# pcb_2.net
KiCad netlist of a schematic drawn in EAGLE
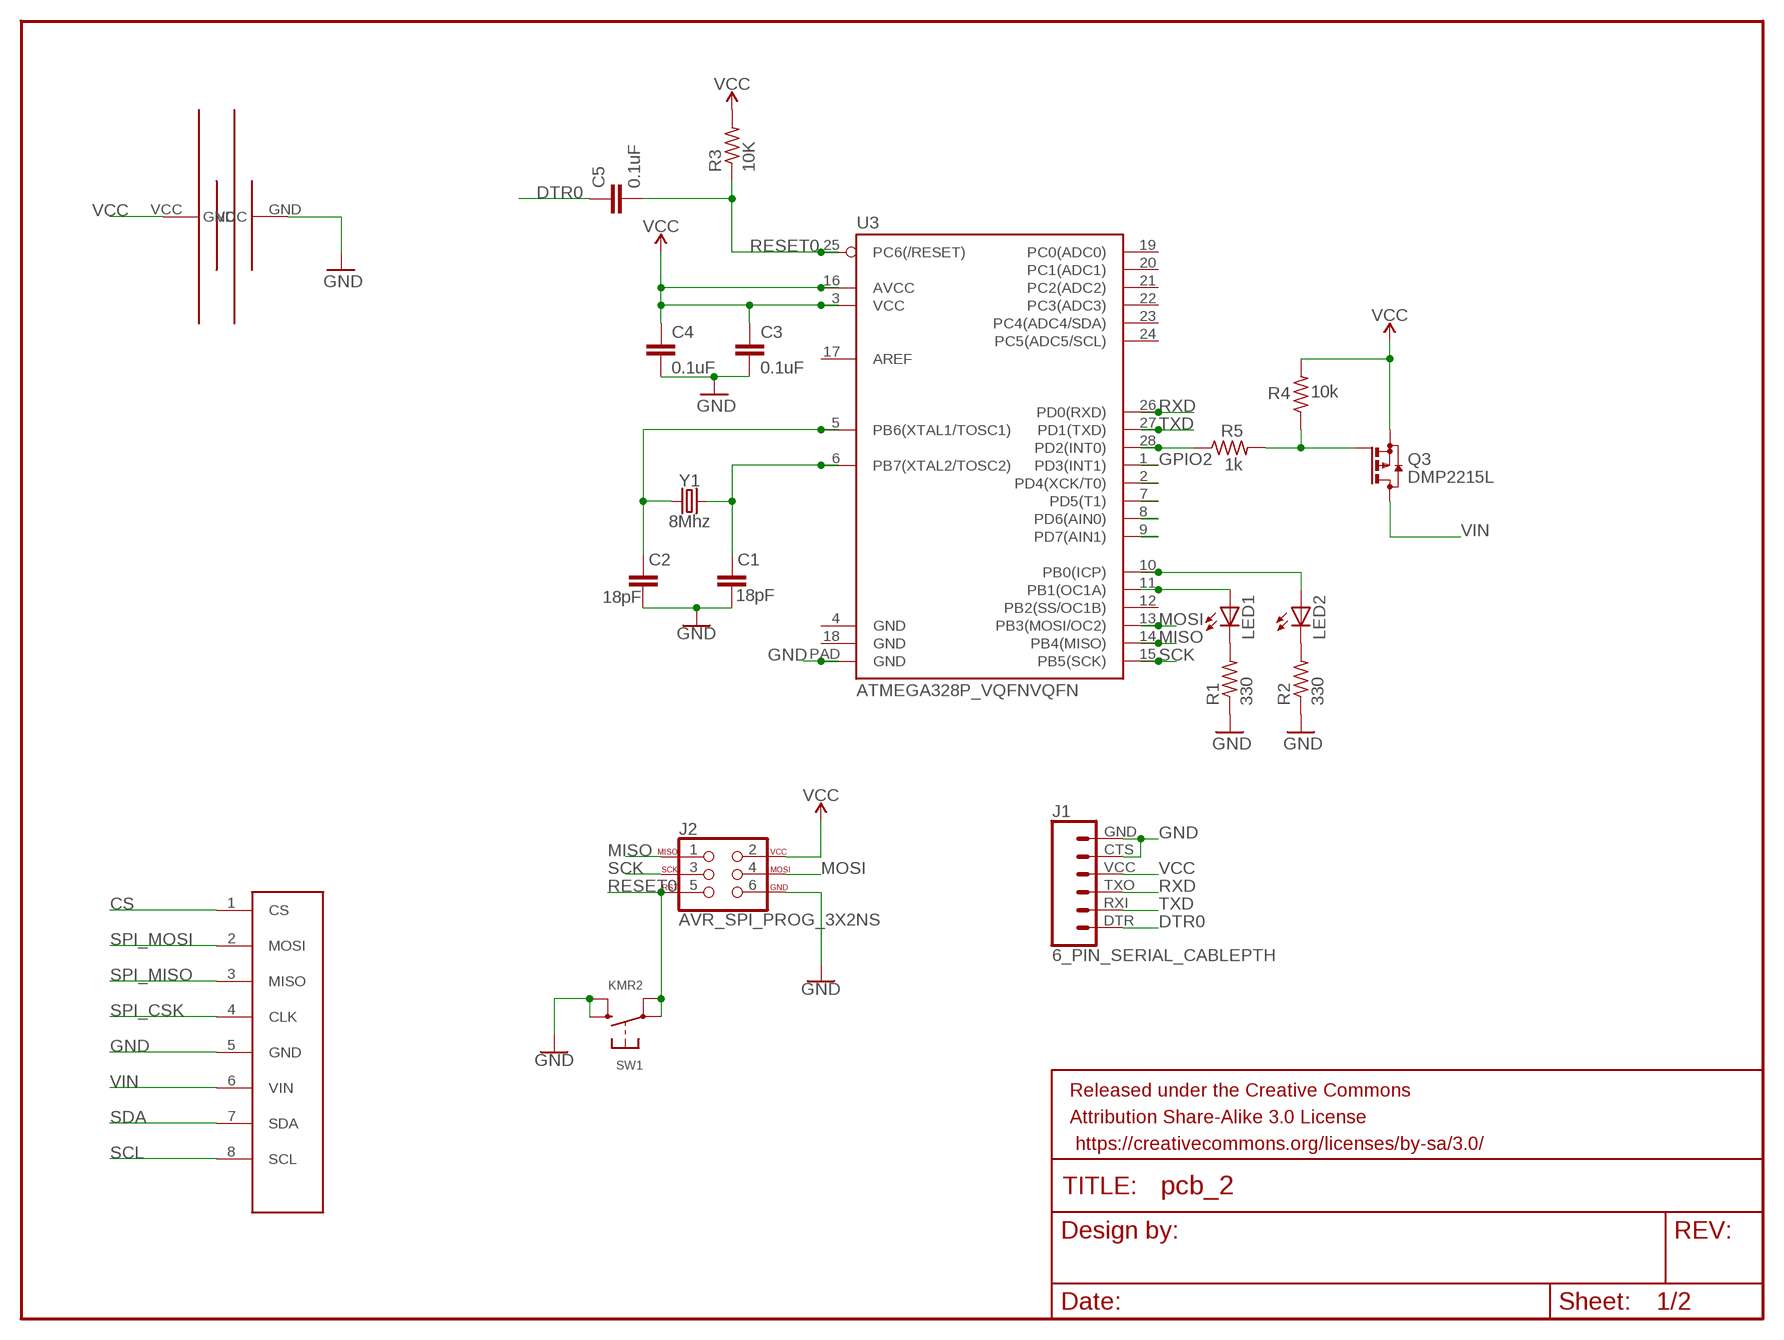
[diagram p0: schematic, sheet 1]
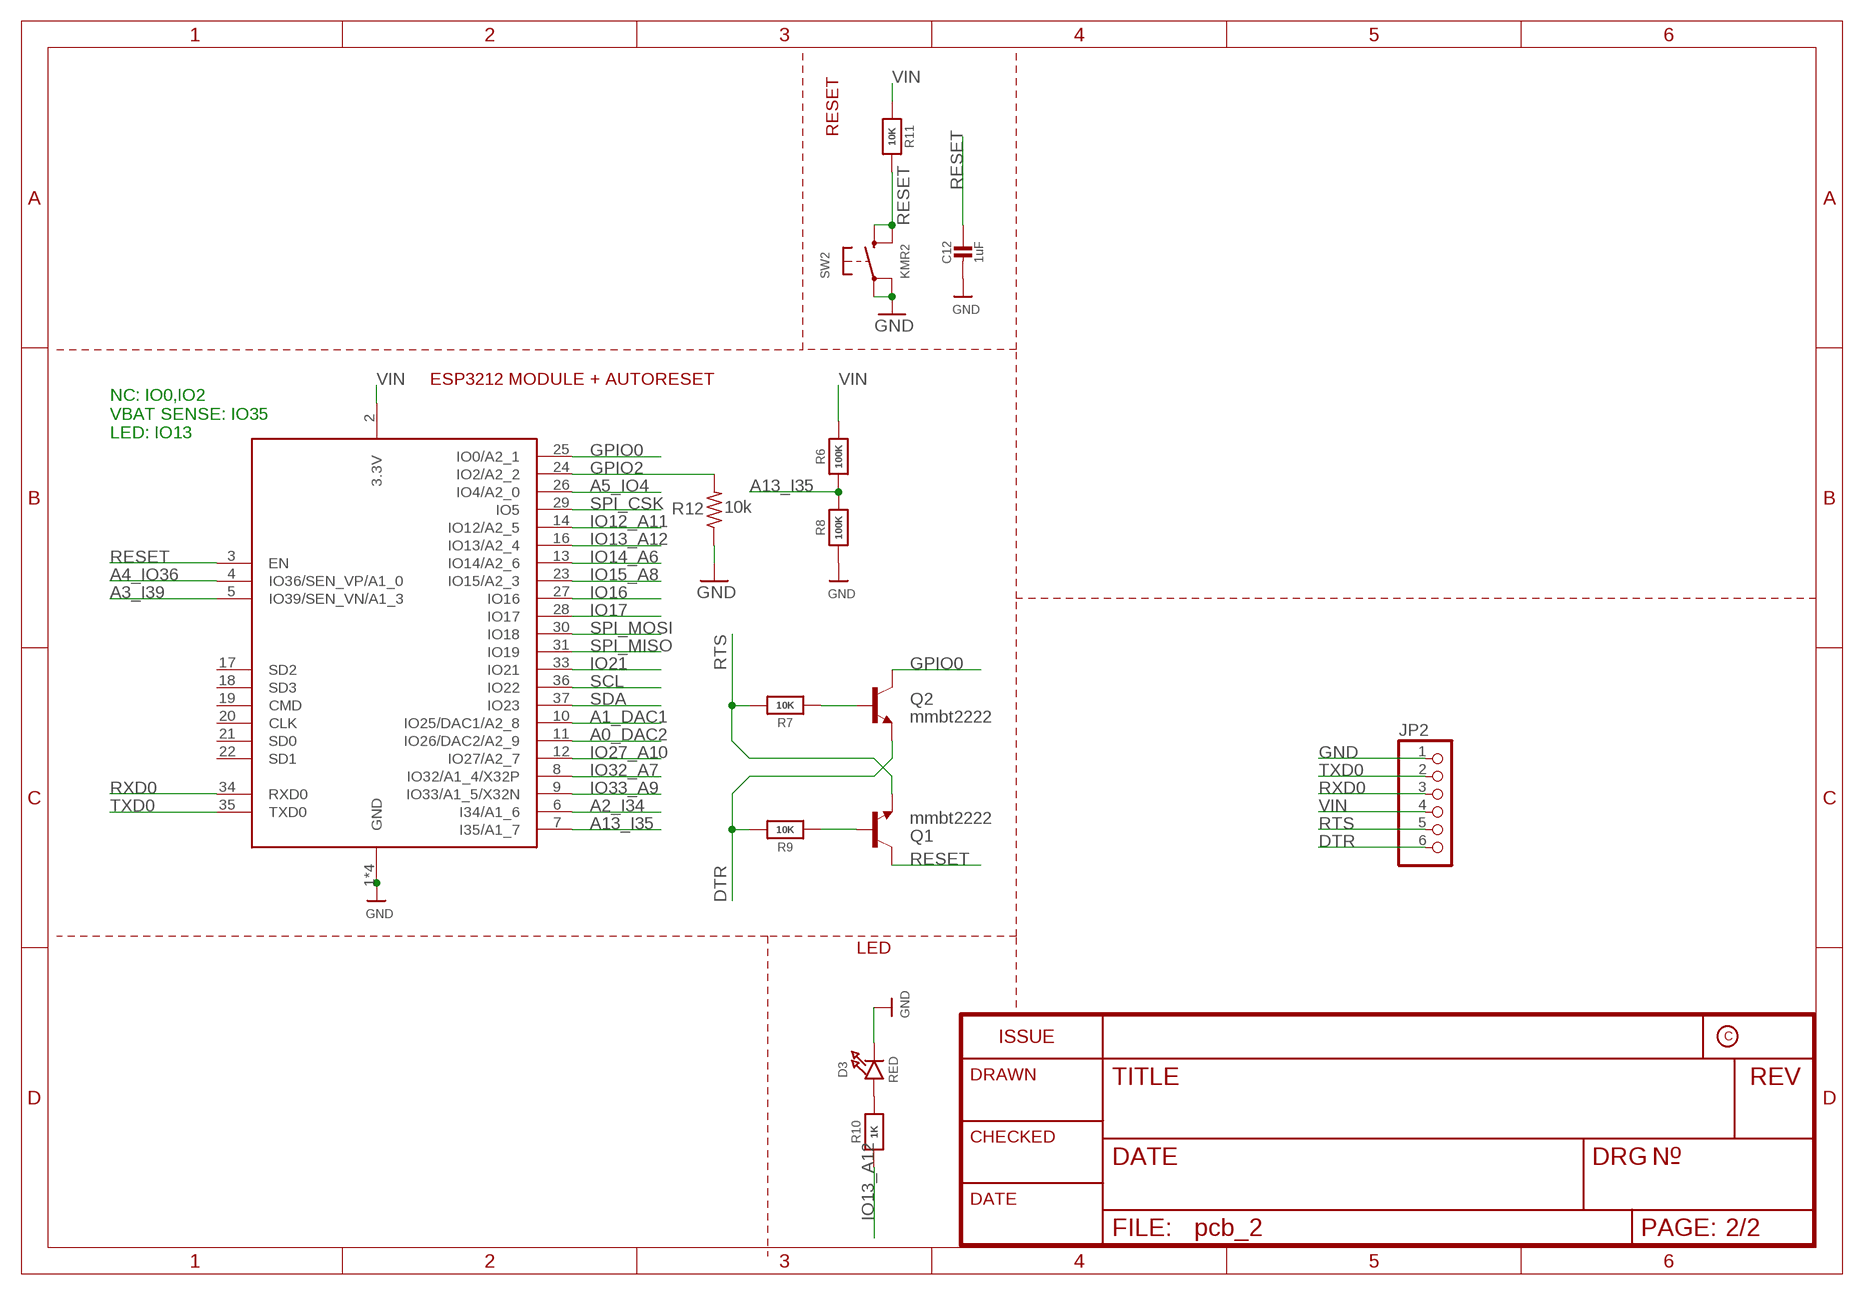
[diagram p1: schematic, sheet 2]

(export (version "E")
  (design (tool "Eeschema 10.0.6"))
  (components
    (comp (ref "C12")
      (value "1uF")
      (footprint "eagle-import:0603-NO")
      (libsource (lib "eagle-import") (part "CAP_CERAMIC0603_NO"))
    )
    (comp (ref "D3")
      (value "RED")
      (footprint "eagle-import:CHIPLED_0805_NOOUTLINE")
      (libsource (lib "eagle-import") (part "LED0805_NOOUTLINE"))
    )
    (comp (ref "JP2")
      (value "PINHD-1X6")
      (footprint "eagle-import:1X06")
      (libsource (lib "eagle-import") (part "PINHD-1X6"))
    )
    (comp (ref "Q1")
      (value "mmbt2222")
      (footprint "eagle-import:SOT23-3")
      (libsource (lib "eagle-import") (part "TRANSISTOR_NPNSOT23-3"))
    )
    (comp (ref "Q2")
      (value "mmbt2222")
      (footprint "eagle-import:SOT23-3")
      (libsource (lib "eagle-import") (part "TRANSISTOR_NPNSOT23-3"))
    )
    (comp (ref "R6")
      (value "100K")
      (footprint "eagle-import:0603-NO")
      (libsource (lib "eagle-import") (part "RESISTOR_0603_NOOUT"))
    )
    (comp (ref "R7")
      (value "10K")
      (footprint "eagle-import:0603-NO")
      (libsource (lib "eagle-import") (part "RESISTOR_0603_NOOUT"))
    )
    (comp (ref "R8")
      (value "100K")
      (footprint "eagle-import:0603-NO")
      (libsource (lib "eagle-import") (part "RESISTOR_0603_NOOUT"))
    )
    (comp (ref "R9")
      (value "10K")
      (footprint "eagle-import:0603-NO")
      (libsource (lib "eagle-import") (part "RESISTOR_0603_NOOUT"))
    )
    (comp (ref "R10")
      (value "1K")
      (footprint "eagle-import:0603-NO")
      (libsource (lib "eagle-import") (part "RESISTOR_0603_NOOUT"))
    )
    (comp (ref "R11")
      (value "10K")
      (footprint "eagle-import:0603-NO")
      (libsource (lib "eagle-import") (part "RESISTOR_0603_NOOUT"))
    )
    (comp (ref "R12")
      (value "10k")
      (footprint "eagle-import:R0603")
      (libsource (lib "eagle-import") (part "resistor_348_R-US_R0603"))
    )
    (comp (ref "SW2")
      (value "KMR2")
      (footprint "eagle-import:BTN_KMR2_4.6X2.8")
      (libsource (lib "eagle-import") (part "SWITCH_TACT_SMT4.6X2.8"))
    )
    (comp (ref "X2")
      (value "ESP32_WROOM32_SKINNY")
      (footprint "eagle-import:WROOM32_SKINNY")
      (libsource (lib "eagle-import") (part "ESP32_WROOM32_SKINNY"))
    )
    (comp (ref "C1")
      (value "18pF")
      (footprint "eagle-import:C0603K")
      (libsource (lib "eagle-import") (part "C-EUC0603K"))
    )
    (comp (ref "C2")
      (value "18pF")
      (footprint "eagle-import:C0603K")
      (libsource (lib "eagle-import") (part "C-EUC0603K"))
    )
    (comp (ref "C3")
      (value "0.1uF")
      (footprint "eagle-import:C0603K")
      (libsource (lib "eagle-import") (part "C-EUC0603K"))
    )
    (comp (ref "C4")
      (value "0.1uF")
      (footprint "eagle-import:C0603K")
      (libsource (lib "eagle-import") (part "C-EUC0603K"))
    )
    (comp (ref "C5")
      (value "0.1uF")
      (footprint "eagle-import:C0603K")
      (libsource (lib "eagle-import") (part "C-EUC0603K"))
    )
    (comp (ref "FRAME1")
      (value "FRAME-LETTER")
      (footprint "eagle-import:CREATIVE_COMMONS")
      (libsource (lib "eagle-import") (part "FRAME-LETTER"))
    )
    (comp (ref "J1")
      (value "6_PIN_SERIAL_CABLEPTH")
      (footprint "eagle-import:FTDI_BASIC")
      (libsource (lib "eagle-import") (part "6_PIN_SERIAL_CABLEPTH"))
    )
    (comp (ref "J2")
      (value "AVR_SPI_PROG_3X2NS")
      (footprint "eagle-import:2X3-NS")
      (libsource (lib "eagle-import") (part "AVR_SPI_PROG_3X2NS"))
    )
    (comp (ref "LED1")
      (value "LED1206")
      (footprint "eagle-import:LED-1206")
      (libsource (lib "eagle-import") (part "LED1206"))
    )
    (comp (ref "LED2")
      (value "LED1206")
      (footprint "eagle-import:LED-1206")
      (libsource (lib "eagle-import") (part "LED1206"))
    )
    (comp (ref "Q3")
      (value "DMP2215L")
      (footprint "eagle-import:SOT23")
      (libsource (lib "eagle-import") (part "BSS84"))
    )
    (comp (ref "R1")
      (value "330")
      (footprint "eagle-import:R0603")
      (libsource (lib "eagle-import") (part "resistor_348_R-US_R0603"))
    )
    (comp (ref "R2")
      (value "330")
      (footprint "eagle-import:R0603")
      (libsource (lib "eagle-import") (part "resistor_348_R-US_R0603"))
    )
    (comp (ref "R3")
      (value "10K")
      (footprint "eagle-import:R0603")
      (libsource (lib "eagle-import") (part "R-US_R0603"))
    )
    (comp (ref "R4")
      (value "10k")
      (footprint "eagle-import:R0603")
      (libsource (lib "eagle-import") (part "resistor_348_R-US_R0603"))
    )
    (comp (ref "R5")
      (value "1k")
      (footprint "eagle-import:R0603")
      (libsource (lib "eagle-import") (part "resistor_348_R-US_R0603"))
    )
    (comp (ref "SW1")
      (value "KMR2")
      (footprint "eagle-import:BTN_KMR2_4.6X2.8")
      (libsource (lib "eagle-import") (part "SWITCH_TACT_SMT4.6X2.8"))
    )
    (comp (ref "U$1")
      (value "BATTERY")
      (footprint "eagle-import:D_PACKAGE")
      (libsource (lib "eagle-import") (part "BATTERY"))
    )
    (comp (ref "U$6")
      (value "FLIRFLIR")
      (footprint "eagle-import:1X08_LONGPADS")
      (libsource (lib "eagle-import") (part "FLIRFLIR"))
    )
    (comp (ref "U3")
      (value "ATMEGA328P_VQFNVQFN")
      (footprint "eagle-import:VQFN-28")
      (libsource (lib "eagle-import") (part "ATMEGA328P_VQFNVQFN"))
    )
    (comp (ref "Y1")
      (value "8Mhz")
      (footprint "eagle-import:HC49UP")
      (libsource (lib "eagle-import") (part "CRYSTALSMD-HC49UP"))
    )
  )
  (nets
    (net (code "1") (name "A0_DAC2") (class "Default")
      (node (ref "X2") (pin "11") (pinfunction "IO26/DAC2/A2_9_11") (pintype "bidirectional"))
    )
    (net (code "2") (name "A1_DAC1") (class "Default")
      (node (ref "X2") (pin "10") (pinfunction "IO25/DAC1/A2_8_10") (pintype "bidirectional"))
    )
    (net (code "3") (name "A2_I34") (class "Default")
      (node (ref "X2") (pin "6") (pinfunction "I34/A1_6_6") (pintype "bidirectional"))
    )
    (net (code "4") (name "A3_I39") (class "Default")
      (node (ref "X2") (pin "5") (pinfunction "IO39/SEN_VN/A1_3_5") (pintype "passive"))
    )
    (net (code "5") (name "A4_IO36") (class "Default")
      (node (ref "X2") (pin "4") (pinfunction "IO36/SEN_VP/A1_0_4") (pintype "passive"))
    )
    (net (code "6") (name "A5_IO4") (class "Default")
      (node (ref "X2") (pin "26") (pinfunction "IO4/A2_0_26") (pintype "bidirectional"))
    )
    (net (code "7") (name "A13_I35") (class "Default")
      (node (ref "R6") (pin "1") (pinfunction "1_1") (pintype "passive"))
      (node (ref "R8") (pin "2") (pinfunction "2_2") (pintype "passive"))
      (node (ref "X2") (pin "7") (pinfunction "I35/A1_7_7") (pintype "bidirectional"))
    )
    (net (code "8") (name "CS") (class "Default")
      (node (ref "U$6") (pin "1") (pinfunction "CS_1") (pintype "bidirectional"))
    )
    (net (code "9") (name "DTR") (class "Default")
      (node (ref "JP2") (pin "6") (pinfunction "6_6") (pintype "passive"))
      (node (ref "Q2") (pin "2") (pinfunction "E_2") (pintype "passive"))
      (node (ref "R9") (pin "2") (pinfunction "2_2") (pintype "passive"))
    )
    (net (code "10") (name "DTR0") (class "Default")
      (node (ref "C5") (pin "1") (pinfunction "1_1") (pintype "passive"))
      (node (ref "J1") (pin "DTR") (pinfunction "1_DTR") (pintype "passive"))
    )
    (net (code "11") (name "GND") (class "Default")
      (node (ref "C1") (pin "2") (pinfunction "2_2") (pintype "passive"))
      (node (ref "C12") (pin "2") (pinfunction "2_2") (pintype "passive"))
      (node (ref "C2") (pin "2") (pinfunction "2_2") (pintype "passive"))
      (node (ref "C3") (pin "2") (pinfunction "2_2") (pintype "passive"))
      (node (ref "C4") (pin "2") (pinfunction "2_2") (pintype "passive"))
      (node (ref "D3") (pin "C") (pinfunction "C_C") (pintype "passive"))
      (node (ref "J1") (pin "CTS") (pinfunction "5_CTS") (pintype "passive"))
      (node (ref "J1") (pin "GND") (pinfunction "6_GND") (pintype "passive"))
      (node (ref "J2") (pin "6") (pinfunction "6_6") (pintype "passive"))
      (node (ref "JP2") (pin "1") (pinfunction "1_1") (pintype "passive"))
      (node (ref "R1") (pin "1") (pinfunction "1_1") (pintype "passive"))
      (node (ref "R12") (pin "1") (pinfunction "1_1") (pintype "passive"))
      (node (ref "R2") (pin "1") (pinfunction "1_1") (pintype "passive"))
      (node (ref "R8") (pin "1") (pinfunction "1_1") (pintype "passive"))
      (node (ref "SW1") (pin "B") (pinfunction "S_B") (pintype "passive"))
      (node (ref "SW1") (pin "B'") (pinfunction "S1_B'") (pintype "passive"))
      (node (ref "SW2") (pin "A") (pinfunction "P_A") (pintype "passive"))
      (node (ref "SW2") (pin "A'") (pinfunction "P1_A'") (pintype "passive"))
      (node (ref "U$1") (pin "GND") (pinfunction "GND_GND") (pintype "bidirectional"))
      (node (ref "U$6") (pin "5") (pinfunction "GND_5") (pintype "bidirectional"))
      (node (ref "U3") (pin "PAD") (pinfunction "GND_PAD") (pintype "bidirectional"))
      (node (ref "X2") (pin "1") (pinfunction "GND_1") (pintype "passive"))
      (node (ref "X2") (pin "15") (pinfunction "GND_15") (pintype "passive"))
      (node (ref "X2") (pin "38") (pinfunction "GND_38") (pintype "passive"))
      (node (ref "X2") (pin "P$1") (pinfunction "GND_P$1") (pintype "passive"))
    )
    (net (code "12") (name "GPIO0") (class "Default")
      (node (ref "Q2") (pin "3") (pinfunction "C_3") (pintype "passive"))
      (node (ref "X2") (pin "25") (pinfunction "IO0/A2_1_25") (pintype "bidirectional"))
    )
    (net (code "13") (name "GPIO2") (class "Default")
      (node (ref "R12") (pin "2") (pinfunction "2_2") (pintype "passive"))
      (node (ref "U3") (pin "1") (pinfunction "PD3(INT1)_1") (pintype "bidirectional"))
      (node (ref "X2") (pin "24") (pinfunction "IO2/A2_2_24") (pintype "bidirectional"))
    )
    (net (code "14") (name "IO12_A11") (class "Default")
      (node (ref "X2") (pin "14") (pinfunction "IO12/A2_5_14") (pintype "bidirectional"))
    )
    (net (code "15") (name "IO13_A12") (class "Default")
      (node (ref "R10") (pin "1") (pinfunction "1_1") (pintype "passive"))
      (node (ref "X2") (pin "16") (pinfunction "IO13/A2_4_16") (pintype "bidirectional"))
    )
    (net (code "16") (name "IO14_A6") (class "Default")
      (node (ref "X2") (pin "13") (pinfunction "IO14/A2_6_13") (pintype "bidirectional"))
    )
    (net (code "17") (name "IO15_A8") (class "Default")
      (node (ref "X2") (pin "23") (pinfunction "IO15/A2_3_23") (pintype "bidirectional"))
    )
    (net (code "18") (name "IO16") (class "Default")
      (node (ref "X2") (pin "27") (pinfunction "IO16_27") (pintype "bidirectional"))
    )
    (net (code "19") (name "IO17") (class "Default")
      (node (ref "X2") (pin "28") (pinfunction "IO17_28") (pintype "bidirectional"))
    )
    (net (code "20") (name "IO21") (class "Default")
      (node (ref "X2") (pin "33") (pinfunction "IO21_33") (pintype "bidirectional"))
    )
    (net (code "21") (name "IO27_A10") (class "Default")
      (node (ref "X2") (pin "12") (pinfunction "IO27/A2_7_12") (pintype "bidirectional"))
    )
    (net (code "22") (name "IO32_A7") (class "Default")
      (node (ref "X2") (pin "8") (pinfunction "IO32/A1_4/X32P_8") (pintype "bidirectional"))
    )
    (net (code "23") (name "IO33_A9") (class "Default")
      (node (ref "X2") (pin "9") (pinfunction "IO33/A1_5/X32N_9") (pintype "bidirectional"))
    )
    (net (code "24") (name "MISO") (class "Default")
      (node (ref "J2") (pin "1") (pinfunction "1_1") (pintype "passive"))
      (node (ref "U3") (pin "14") (pinfunction "PB4(MISO)_14") (pintype "bidirectional"))
    )
    (net (code "25") (name "MOSI") (class "Default")
      (node (ref "J2") (pin "4") (pinfunction "4_4") (pintype "passive"))
      (node (ref "U3") (pin "13") (pinfunction "PB3(MOSI/OC2)_13") (pintype "bidirectional"))
    )
    (net (code "26") (name "Net-(D3-PadA)") (class "Default")
      (node (ref "D3") (pin "A") (pinfunction "A_A") (pintype "passive"))
      (node (ref "R10") (pin "2") (pinfunction "2_2") (pintype "passive"))
    )
    (net (code "27") (name "Net-(LED1-PadC)") (class "Default")
      (node (ref "LED1") (pin "C") (pinfunction "C_C") (pintype "passive"))
      (node (ref "R1") (pin "2") (pinfunction "2_2") (pintype "passive"))
    )
    (net (code "28") (name "Net-(LED2-PadC)") (class "Default")
      (node (ref "LED2") (pin "C") (pinfunction "C_C") (pintype "passive"))
      (node (ref "R2") (pin "2") (pinfunction "2_2") (pintype "passive"))
    )
    (net (code "29") (name "Net-(Q1-B)") (class "Default")
      (node (ref "Q1") (pin "1") (pinfunction "B_1") (pintype "passive"))
      (node (ref "R9") (pin "1") (pinfunction "1_1") (pintype "passive"))
    )
    (net (code "30") (name "Net-(Q2-B)") (class "Default")
      (node (ref "Q2") (pin "1") (pinfunction "B_1") (pintype "passive"))
      (node (ref "R7") (pin "1") (pinfunction "1_1") (pintype "passive"))
    )
    (net (code "31") (name "Net-(Q3-G)") (class "Default")
      (node (ref "Q3") (pin "1") (pinfunction "G_1") (pintype "passive"))
      (node (ref "R4") (pin "1") (pinfunction "1_1") (pintype "passive"))
      (node (ref "R5") (pin "2") (pinfunction "2_2") (pintype "passive"))
    )
    (net (code "32") (name "Net-(U3-PB0(ICP))") (class "Default")
      (node (ref "LED2") (pin "A") (pinfunction "A_A") (pintype "passive"))
      (node (ref "U3") (pin "10") (pinfunction "PB0(ICP)_10") (pintype "bidirectional"))
    )
    (net (code "33") (name "Net-(U3-PB1(OC1A))") (class "Default")
      (node (ref "LED1") (pin "A") (pinfunction "A_A") (pintype "passive"))
      (node (ref "U3") (pin "11") (pinfunction "PB1(OC1A)_11") (pintype "bidirectional"))
    )
    (net (code "34") (name "Net-(U3-PB6(XTAL1{slash}TOSC1))") (class "Default")
      (node (ref "C2") (pin "1") (pinfunction "1_1") (pintype "passive"))
      (node (ref "U3") (pin "5") (pinfunction "PB6(XTAL1/TOSC1)_5") (pintype "bidirectional"))
      (node (ref "Y1") (pin "1") (pinfunction "1_1") (pintype "passive"))
    )
    (net (code "35") (name "Net-(U3-PB7(XTAL2{slash}TOSC2))") (class "Default")
      (node (ref "C1") (pin "1") (pinfunction "1_1") (pintype "passive"))
      (node (ref "U3") (pin "6") (pinfunction "PB7(XTAL2/TOSC2)_6") (pintype "bidirectional"))
      (node (ref "Y1") (pin "2") (pinfunction "2_2") (pintype "passive"))
    )
    (net (code "36") (name "Net-(U3-PD2(INT0))") (class "Default")
      (node (ref "R5") (pin "1") (pinfunction "1_1") (pintype "passive"))
      (node (ref "U3") (pin "28") (pinfunction "PD2(INT0)_28") (pintype "bidirectional"))
    )
    (net (code "37") (name "RESET") (class "Default")
      (node (ref "C12") (pin "1") (pinfunction "1_1") (pintype "passive"))
      (node (ref "Q1") (pin "3") (pinfunction "C_3") (pintype "passive"))
      (node (ref "R11") (pin "2") (pinfunction "2_2") (pintype "passive"))
      (node (ref "SW2") (pin "B") (pinfunction "S_B") (pintype "passive"))
      (node (ref "SW2") (pin "B'") (pinfunction "S1_B'") (pintype "passive"))
      (node (ref "X2") (pin "3") (pinfunction "EN_3") (pintype "input"))
    )
    (net (code "38") (name "RESET0") (class "Default")
      (node (ref "C5") (pin "2") (pinfunction "2_2") (pintype "passive"))
      (node (ref "J2") (pin "5") (pinfunction "5_5") (pintype "passive"))
      (node (ref "R3") (pin "1") (pinfunction "1_1") (pintype "passive"))
      (node (ref "SW1") (pin "A") (pinfunction "P_A") (pintype "passive"))
      (node (ref "SW1") (pin "A'") (pinfunction "P1_A'") (pintype "passive"))
      (node (ref "U3") (pin "25") (pinfunction "PC6(/RESET)_25") (pintype "bidirectional"))
    )
    (net (code "39") (name "RTS") (class "Default")
      (node (ref "JP2") (pin "5") (pinfunction "5_5") (pintype "passive"))
      (node (ref "Q1") (pin "2") (pinfunction "E_2") (pintype "passive"))
      (node (ref "R7") (pin "2") (pinfunction "2_2") (pintype "passive"))
    )
    (net (code "40") (name "RXD") (class "Default")
      (node (ref "J1") (pin "TXO") (pinfunction "3_TXO") (pintype "passive"))
      (node (ref "U3") (pin "26") (pinfunction "PD0(RXD)_26") (pintype "bidirectional"))
    )
    (net (code "41") (name "RXD0") (class "Default")
      (node (ref "JP2") (pin "3") (pinfunction "3_3") (pintype "passive"))
      (node (ref "X2") (pin "34") (pinfunction "RXD0_34") (pintype "input"))
    )
    (net (code "42") (name "SCK") (class "Default")
      (node (ref "J2") (pin "3") (pinfunction "3_3") (pintype "passive"))
      (node (ref "U3") (pin "15") (pinfunction "PB5(SCK)_15") (pintype "bidirectional"))
    )
    (net (code "43") (name "SCL") (class "Default")
      (node (ref "U$6") (pin "8") (pinfunction "SCL_8") (pintype "bidirectional"))
      (node (ref "X2") (pin "36") (pinfunction "IO22_36") (pintype "bidirectional"))
    )
    (net (code "44") (name "SDA") (class "Default")
      (node (ref "U$6") (pin "7") (pinfunction "SDA_7") (pintype "bidirectional"))
      (node (ref "X2") (pin "37") (pinfunction "IO23_37") (pintype "bidirectional"))
    )
    (net (code "45") (name "SPI_CSK") (class "Default")
      (node (ref "U$6") (pin "4") (pinfunction "CLK_4") (pintype "bidirectional"))
      (node (ref "X2") (pin "29") (pinfunction "IO5_29") (pintype "bidirectional"))
    )
    (net (code "46") (name "SPI_MISO") (class "Default")
      (node (ref "U$6") (pin "3") (pinfunction "MISO_3") (pintype "bidirectional"))
      (node (ref "X2") (pin "31") (pinfunction "IO19_31") (pintype "bidirectional"))
    )
    (net (code "47") (name "SPI_MOSI") (class "Default")
      (node (ref "U$6") (pin "2") (pinfunction "MOSI_2") (pintype "bidirectional"))
      (node (ref "X2") (pin "30") (pinfunction "IO18_30") (pintype "bidirectional"))
    )
    (net (code "48") (name "TXD") (class "Default")
      (node (ref "J1") (pin "RXI") (pinfunction "2_RXI") (pintype "passive"))
      (node (ref "U3") (pin "27") (pinfunction "PD1(TXD)_27") (pintype "bidirectional"))
    )
    (net (code "49") (name "TXD0") (class "Default")
      (node (ref "JP2") (pin "2") (pinfunction "2_2") (pintype "passive"))
      (node (ref "X2") (pin "35") (pinfunction "TXD0_35") (pintype "output"))
    )
    (net (code "50") (name "VCC") (class "Default")
      (node (ref "C3") (pin "1") (pinfunction "1_1") (pintype "passive"))
      (node (ref "C4") (pin "1") (pinfunction "1_1") (pintype "passive"))
      (node (ref "J1") (pin "VCC") (pinfunction "4_VCC") (pintype "passive"))
      (node (ref "J2") (pin "2") (pinfunction "2_2") (pintype "passive"))
      (node (ref "Q3") (pin "2") (pinfunction "S_2") (pintype "passive"))
      (node (ref "R3") (pin "2") (pinfunction "2_2") (pintype "passive"))
      (node (ref "R4") (pin "2") (pinfunction "2_2") (pintype "passive"))
      (node (ref "U$1") (pin "VCC") (pinfunction "VCC_VCC") (pintype "bidirectional"))
      (node (ref "U3") (pin "16") (pinfunction "AVCC_16") (pintype "bidirectional"))
      (node (ref "U3") (pin "3") (pinfunction "VCC_3") (pintype "bidirectional"))
    )
    (net (code "51") (name "VIN") (class "Default")
      (node (ref "JP2") (pin "4") (pinfunction "4_4") (pintype "passive"))
      (node (ref "Q3") (pin "3") (pinfunction "D_3") (pintype "passive"))
      (node (ref "R11") (pin "1") (pinfunction "1_1") (pintype "passive"))
      (node (ref "R6") (pin "2") (pinfunction "2_2") (pintype "passive"))
      (node (ref "U$6") (pin "6") (pinfunction "VIN_6") (pintype "bidirectional"))
      (node (ref "X2") (pin "2") (pinfunction "3.3V_2") (pintype "passive"))
    )
    (net (code "52") (name "unconnected-(U3-AREF-Pad17)") (class "Default")
      (node (ref "U3") (pin "17") (pinfunction "AREF_17") (pintype "bidirectional"))
    )
    (net (code "53") (name "unconnected-(U3-GND-Pad4)") (class "Default")
      (node (ref "U3") (pin "4") (pinfunction "GND_4") (pintype "bidirectional"))
    )
    (net (code "54") (name "unconnected-(U3-GND-Pad18)") (class "Default")
      (node (ref "U3") (pin "18") (pinfunction "GND_18") (pintype "bidirectional"))
    )
    (net (code "55") (name "unconnected-(U3-PB2(SS{slash}OC1B)-Pad12)") (class "Default")
      (node (ref "U3") (pin "12") (pinfunction "PB2(SS/OC1B)_12") (pintype "bidirectional"))
    )
    (net (code "56") (name "unconnected-(U3-PC0(ADC0)-Pad19)") (class "Default")
      (node (ref "U3") (pin "19") (pinfunction "PC0(ADC0)_19") (pintype "bidirectional"))
    )
    (net (code "57") (name "unconnected-(U3-PC1(ADC1)-Pad20)") (class "Default")
      (node (ref "U3") (pin "20") (pinfunction "PC1(ADC1)_20") (pintype "bidirectional"))
    )
    (net (code "58") (name "unconnected-(U3-PC2(ADC2)-Pad21)") (class "Default")
      (node (ref "U3") (pin "21") (pinfunction "PC2(ADC2)_21") (pintype "bidirectional"))
    )
    (net (code "59") (name "unconnected-(U3-PC3(ADC3)-Pad22)") (class "Default")
      (node (ref "U3") (pin "22") (pinfunction "PC3(ADC3)_22") (pintype "bidirectional"))
    )
    (net (code "60") (name "unconnected-(U3-PC4(ADC4{slash}SDA)-Pad23)") (class "Default")
      (node (ref "U3") (pin "23") (pinfunction "PC4(ADC4/SDA)_23") (pintype "bidirectional"))
    )
    (net (code "61") (name "unconnected-(U3-PC5(ADC5{slash}SCL)-Pad24)") (class "Default")
      (node (ref "U3") (pin "24") (pinfunction "PC5(ADC5/SCL)_24") (pintype "bidirectional"))
    )
    (net (code "62") (name "unconnected-(U3-PD4(XCK{slash}T0)-Pad2)") (class "Default")
      (node (ref "U3") (pin "2") (pinfunction "PD4(XCK/T0)_2") (pintype "bidirectional"))
    )
    (net (code "63") (name "unconnected-(U3-PD5(T1)-Pad7)") (class "Default")
      (node (ref "U3") (pin "7") (pinfunction "PD5(T1)_7") (pintype "bidirectional"))
    )
    (net (code "64") (name "unconnected-(U3-PD6(AIN0)-Pad8)") (class "Default")
      (node (ref "U3") (pin "8") (pinfunction "PD6(AIN0)_8") (pintype "bidirectional"))
    )
    (net (code "65") (name "unconnected-(U3-PD7(AIN1)-Pad9)") (class "Default")
      (node (ref "U3") (pin "9") (pinfunction "PD7(AIN1)_9") (pintype "bidirectional"))
    )
    (net (code "66") (name "unconnected-(X2-CLK-Pad20)") (class "Default")
      (node (ref "X2") (pin "20") (pinfunction "CLK_20") (pintype "bidirectional"))
    )
    (net (code "67") (name "unconnected-(X2-CMD-Pad19)") (class "Default")
      (node (ref "X2") (pin "19") (pinfunction "CMD_19") (pintype "bidirectional"))
    )
    (net (code "68") (name "unconnected-(X2-SD0-Pad21)") (class "Default")
      (node (ref "X2") (pin "21") (pinfunction "SD0_21") (pintype "bidirectional"))
    )
    (net (code "69") (name "unconnected-(X2-SD1-Pad22)") (class "Default")
      (node (ref "X2") (pin "22") (pinfunction "SD1_22") (pintype "bidirectional"))
    )
    (net (code "70") (name "unconnected-(X2-SD2-Pad17)") (class "Default")
      (node (ref "X2") (pin "17") (pinfunction "SD2_17") (pintype "bidirectional"))
    )
    (net (code "71") (name "unconnected-(X2-SD3-Pad18)") (class "Default")
      (node (ref "X2") (pin "18") (pinfunction "SD3_18") (pintype "bidirectional"))
    )
  )
)
